# KeyChaininoTHT.net
KiCad netlist of a schematic drawn in EAGLE
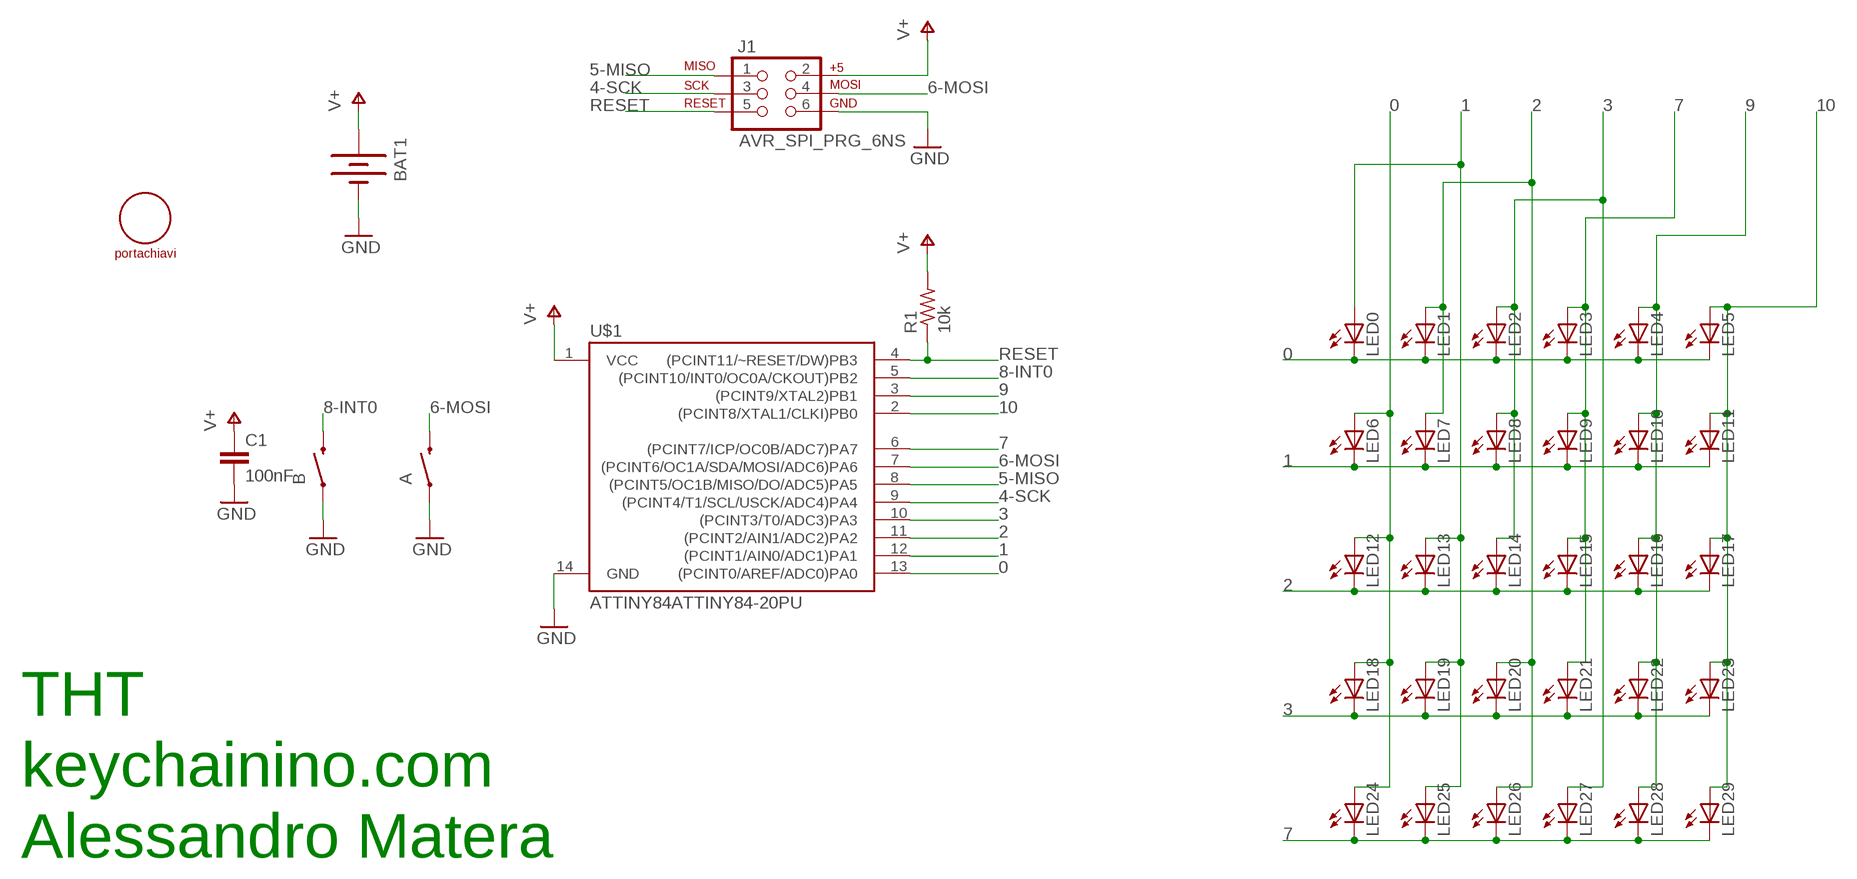
[diagram p0: schematic, sheet 1]

(export (version "E")
  (design (tool "Eeschema 10.0.6"))
  (components
    (comp (ref "A")
      (value "SWITCH-MOMENTARY-2PTH")
      (footprint "eagle-import:TACTILE-PTH")
      (libsource (lib "eagle-import") (part "SWITCH-MOMENTARY-2PTH"))
    )
    (comp (ref "B")
      (value "SWITCH-MOMENTARY-2PTH")
      (footprint "eagle-import:TACTILE-PTH")
      (libsource (lib "eagle-import") (part "SWITCH-MOMENTARY-2PTH"))
    )
    (comp (ref "BAT1")
      (value "BATTERY20PTH")
      (footprint "eagle-import:BATTCOM_20MM_PTH")
      (libsource (lib "eagle-import") (part "BATTERY20PTH"))
    )
    (comp (ref "C1")
      (value "100nF")
      (footprint "eagle-import:CAP-PTH-5MM")
      (libsource (lib "eagle-import") (part "CAPPTH1"))
    )
    (comp (ref "J1")
      (value "AVR_SPI_PRG_6NS")
      (footprint "eagle-import:2X3-NS")
      (libsource (lib "eagle-import") (part "AVR_SPI_PRG_6NS"))
    )
    (comp (ref "LED0")
      (value "LED5MM-KIT")
      (footprint "eagle-import:LED5MM-KIT")
      (libsource (lib "eagle-import") (part "LED5MM-KIT"))
    )
    (comp (ref "LED1")
      (value "LED5MM-KIT")
      (footprint "eagle-import:LED5MM-KIT")
      (libsource (lib "eagle-import") (part "LED5MM-KIT"))
    )
    (comp (ref "LED2")
      (value "LED5MM-KIT")
      (footprint "eagle-import:LED5MM-KIT")
      (libsource (lib "eagle-import") (part "LED5MM-KIT"))
    )
    (comp (ref "LED3")
      (value "LED5MM-KIT")
      (footprint "eagle-import:LED5MM-KIT")
      (libsource (lib "eagle-import") (part "LED5MM-KIT"))
    )
    (comp (ref "LED4")
      (value "LED5MM-KIT")
      (footprint "eagle-import:LED5MM-KIT")
      (libsource (lib "eagle-import") (part "LED5MM-KIT"))
    )
    (comp (ref "LED5")
      (value "LED5MM-KIT")
      (footprint "eagle-import:LED5MM-KIT")
      (libsource (lib "eagle-import") (part "LED5MM-KIT"))
    )
    (comp (ref "LED6")
      (value "LED5MM-KIT")
      (footprint "eagle-import:LED5MM-KIT")
      (libsource (lib "eagle-import") (part "LED5MM-KIT"))
    )
    (comp (ref "LED7")
      (value "LED5MM-KIT")
      (footprint "eagle-import:LED5MM-KIT")
      (libsource (lib "eagle-import") (part "LED5MM-KIT"))
    )
    (comp (ref "LED8")
      (value "LED5MM-KIT")
      (footprint "eagle-import:LED5MM-KIT")
      (libsource (lib "eagle-import") (part "LED5MM-KIT"))
    )
    (comp (ref "LED9")
      (value "LED5MM-KIT")
      (footprint "eagle-import:LED5MM-KIT")
      (libsource (lib "eagle-import") (part "LED5MM-KIT"))
    )
    (comp (ref "LED10")
      (value "LED5MM-KIT")
      (footprint "eagle-import:LED5MM-KIT")
      (libsource (lib "eagle-import") (part "LED5MM-KIT"))
    )
    (comp (ref "LED11")
      (value "LED5MM-KIT")
      (footprint "eagle-import:LED5MM-KIT")
      (libsource (lib "eagle-import") (part "LED5MM-KIT"))
    )
    (comp (ref "LED12")
      (value "LED5MM-KIT")
      (footprint "eagle-import:LED5MM-KIT")
      (libsource (lib "eagle-import") (part "LED5MM-KIT"))
    )
    (comp (ref "LED13")
      (value "LED5MM-KIT")
      (footprint "eagle-import:LED5MM-KIT")
      (libsource (lib "eagle-import") (part "LED5MM-KIT"))
    )
    (comp (ref "LED14")
      (value "LED5MM-KIT")
      (footprint "eagle-import:LED5MM-KIT")
      (libsource (lib "eagle-import") (part "LED5MM-KIT"))
    )
    (comp (ref "LED15")
      (value "LED5MM-KIT")
      (footprint "eagle-import:LED5MM-KIT")
      (libsource (lib "eagle-import") (part "LED5MM-KIT"))
    )
    (comp (ref "LED16")
      (value "LED5MM-KIT")
      (footprint "eagle-import:LED5MM-KIT")
      (libsource (lib "eagle-import") (part "LED5MM-KIT"))
    )
    (comp (ref "LED17")
      (value "LED5MM-KIT")
      (footprint "eagle-import:LED5MM-KIT")
      (libsource (lib "eagle-import") (part "LED5MM-KIT"))
    )
    (comp (ref "LED18")
      (value "LED5MM-KIT")
      (footprint "eagle-import:LED5MM-KIT")
      (libsource (lib "eagle-import") (part "LED5MM-KIT"))
    )
    (comp (ref "LED19")
      (value "LED5MM-KIT")
      (footprint "eagle-import:LED5MM-KIT")
      (libsource (lib "eagle-import") (part "LED5MM-KIT"))
    )
    (comp (ref "LED20")
      (value "LED5MM-KIT")
      (footprint "eagle-import:LED5MM-KIT")
      (libsource (lib "eagle-import") (part "LED5MM-KIT"))
    )
    (comp (ref "LED21")
      (value "LED5MM-KIT")
      (footprint "eagle-import:LED5MM-KIT")
      (libsource (lib "eagle-import") (part "LED5MM-KIT"))
    )
    (comp (ref "LED22")
      (value "LED5MM-KIT")
      (footprint "eagle-import:LED5MM-KIT")
      (libsource (lib "eagle-import") (part "LED5MM-KIT"))
    )
    (comp (ref "LED23")
      (value "LED5MM-KIT")
      (footprint "eagle-import:LED5MM-KIT")
      (libsource (lib "eagle-import") (part "LED5MM-KIT"))
    )
    (comp (ref "LED24")
      (value "LED5MM-KIT")
      (footprint "eagle-import:LED5MM-KIT")
      (libsource (lib "eagle-import") (part "LED5MM-KIT"))
    )
    (comp (ref "LED25")
      (value "LED5MM-KIT")
      (footprint "eagle-import:LED5MM-KIT")
      (libsource (lib "eagle-import") (part "LED5MM-KIT"))
    )
    (comp (ref "LED26")
      (value "LED5MM-KIT")
      (footprint "eagle-import:LED5MM-KIT")
      (libsource (lib "eagle-import") (part "LED5MM-KIT"))
    )
    (comp (ref "LED27")
      (value "LED5MM-KIT")
      (footprint "eagle-import:LED5MM-KIT")
      (libsource (lib "eagle-import") (part "LED5MM-KIT"))
    )
    (comp (ref "LED28")
      (value "LED5MM-KIT")
      (footprint "eagle-import:LED5MM-KIT")
      (libsource (lib "eagle-import") (part "LED5MM-KIT"))
    )
    (comp (ref "LED29")
      (value "LED5MM-KIT")
      (footprint "eagle-import:LED5MM-KIT")
      (libsource (lib "eagle-import") (part "LED5MM-KIT"))
    )
    (comp (ref "R1")
      (value "10k")
      (footprint "eagle-import:R1206")
      (libsource (lib "eagle-import") (part "R-US_R1206"))
    )
    (comp (ref "U$1")
      (value "ATTINY84ATTINY84-20PU")
      (footprint "eagle-import:DIL14")
      (libsource (lib "eagle-import") (part "ATTINY84ATTINY84-20PU"))
    )
    (comp (ref "U$2")
      (value "ANELLO-PORTACHIAVI")
      (footprint "eagle-import:HOLE-PORTACHIAVI")
      (libsource (lib "eagle-import") (part "ANELLO-PORTACHIAVI"))
    )
  )
  (nets
    (net (code "1") (name "/0") (class "Default")
      (node (ref "LED0") (pin "K") (pinfunction "C_K") (pintype "passive"))
      (node (ref "LED1") (pin "K") (pinfunction "C_K") (pintype "passive"))
      (node (ref "LED12") (pin "A") (pinfunction "A_A") (pintype "passive"))
      (node (ref "LED18") (pin "A") (pinfunction "A_A") (pintype "passive"))
      (node (ref "LED2") (pin "K") (pinfunction "C_K") (pintype "passive"))
      (node (ref "LED24") (pin "A") (pinfunction "A_A") (pintype "passive"))
      (node (ref "LED3") (pin "K") (pinfunction "C_K") (pintype "passive"))
      (node (ref "LED4") (pin "K") (pinfunction "C_K") (pintype "passive"))
      (node (ref "LED5") (pin "K") (pinfunction "C_K") (pintype "passive"))
      (node (ref "LED6") (pin "A") (pinfunction "A_A") (pintype "passive"))
      (node (ref "U$1") (pin "13") (pinfunction "(PCINT0/AREF/ADC0)PA0_13") (pintype "bidirectional"))
    )
    (net (code "2") (name "/1") (class "Default")
      (node (ref "LED0") (pin "A") (pinfunction "A_A") (pintype "passive"))
      (node (ref "LED10") (pin "K") (pinfunction "C_K") (pintype "passive"))
      (node (ref "LED11") (pin "K") (pinfunction "C_K") (pintype "passive"))
      (node (ref "LED13") (pin "A") (pinfunction "A_A") (pintype "passive"))
      (node (ref "LED19") (pin "A") (pinfunction "A_A") (pintype "passive"))
      (node (ref "LED25") (pin "A") (pinfunction "A_A") (pintype "passive"))
      (node (ref "LED6") (pin "K") (pinfunction "C_K") (pintype "passive"))
      (node (ref "LED7") (pin "K") (pinfunction "C_K") (pintype "passive"))
      (node (ref "LED8") (pin "K") (pinfunction "C_K") (pintype "passive"))
      (node (ref "LED9") (pin "K") (pinfunction "C_K") (pintype "passive"))
      (node (ref "U$1") (pin "12") (pinfunction "(PCINT1/AIN0/ADC1)PA1_12") (pintype "bidirectional"))
    )
    (net (code "3") (name "/2") (class "Default")
      (node (ref "LED1") (pin "A") (pinfunction "A_A") (pintype "passive"))
      (node (ref "LED12") (pin "K") (pinfunction "C_K") (pintype "passive"))
      (node (ref "LED13") (pin "K") (pinfunction "C_K") (pintype "passive"))
      (node (ref "LED14") (pin "K") (pinfunction "C_K") (pintype "passive"))
      (node (ref "LED15") (pin "K") (pinfunction "C_K") (pintype "passive"))
      (node (ref "LED16") (pin "K") (pinfunction "C_K") (pintype "passive"))
      (node (ref "LED17") (pin "K") (pinfunction "C_K") (pintype "passive"))
      (node (ref "LED20") (pin "A") (pinfunction "A_A") (pintype "passive"))
      (node (ref "LED26") (pin "A") (pinfunction "A_A") (pintype "passive"))
      (node (ref "LED7") (pin "A") (pinfunction "A_A") (pintype "passive"))
      (node (ref "U$1") (pin "11") (pinfunction "(PCINT2/AIN1/ADC2)PA2_11") (pintype "bidirectional"))
    )
    (net (code "4") (name "/3") (class "Default")
      (node (ref "LED14") (pin "A") (pinfunction "A_A") (pintype "passive"))
      (node (ref "LED18") (pin "K") (pinfunction "C_K") (pintype "passive"))
      (node (ref "LED19") (pin "K") (pinfunction "C_K") (pintype "passive"))
      (node (ref "LED2") (pin "A") (pinfunction "A_A") (pintype "passive"))
      (node (ref "LED20") (pin "K") (pinfunction "C_K") (pintype "passive"))
      (node (ref "LED21") (pin "K") (pinfunction "C_K") (pintype "passive"))
      (node (ref "LED22") (pin "K") (pinfunction "C_K") (pintype "passive"))
      (node (ref "LED23") (pin "K") (pinfunction "C_K") (pintype "passive"))
      (node (ref "LED27") (pin "A") (pinfunction "A_A") (pintype "passive"))
      (node (ref "LED8") (pin "A") (pinfunction "A_A") (pintype "passive"))
      (node (ref "U$1") (pin "10") (pinfunction "(PCINT3/T0/ADC3)PA3_10") (pintype "bidirectional"))
    )
    (net (code "5") (name "/4-SCK") (class "Default")
      (node (ref "J1") (pin "3") (pinfunction "3_3") (pintype "passive"))
      (node (ref "U$1") (pin "9") (pinfunction "(PCINT4/T1/SCL/USCK/ADC4)PA4_9") (pintype "bidirectional"))
    )
    (net (code "6") (name "/5-MISO") (class "Default")
      (node (ref "J1") (pin "1") (pinfunction "1_1") (pintype "passive"))
      (node (ref "U$1") (pin "8") (pinfunction "(PCINT5/OC1B/MISO/DO/ADC5)PA5_8") (pintype "bidirectional"))
    )
    (net (code "7") (name "/6-MOSI") (class "Default")
      (node (ref "A") (pin "3") (pinfunction "2_3") (pintype "passive"))
      (node (ref "J1") (pin "4") (pinfunction "4_4") (pintype "passive"))
      (node (ref "U$1") (pin "7") (pinfunction "(PCINT6/OC1A/SDA/MOSI/ADC6)PA6_7") (pintype "bidirectional"))
    )
    (net (code "8") (name "/7") (class "Default")
      (node (ref "LED15") (pin "A") (pinfunction "A_A") (pintype "passive"))
      (node (ref "LED21") (pin "A") (pinfunction "A_A") (pintype "passive"))
      (node (ref "LED24") (pin "K") (pinfunction "C_K") (pintype "passive"))
      (node (ref "LED25") (pin "K") (pinfunction "C_K") (pintype "passive"))
      (node (ref "LED26") (pin "K") (pinfunction "C_K") (pintype "passive"))
      (node (ref "LED27") (pin "K") (pinfunction "C_K") (pintype "passive"))
      (node (ref "LED28") (pin "K") (pinfunction "C_K") (pintype "passive"))
      (node (ref "LED29") (pin "K") (pinfunction "C_K") (pintype "passive"))
      (node (ref "LED3") (pin "A") (pinfunction "A_A") (pintype "passive"))
      (node (ref "LED9") (pin "A") (pinfunction "A_A") (pintype "passive"))
      (node (ref "U$1") (pin "6") (pinfunction "(PCINT7/ICP/OC0B/ADC7)PA7_6") (pintype "bidirectional"))
    )
    (net (code "9") (name "/8-INT0") (class "Default")
      (node (ref "B") (pin "3") (pinfunction "2_3") (pintype "passive"))
      (node (ref "U$1") (pin "5") (pinfunction "(PCINT10/INT0/OC0A/CKOUT)PB2_5") (pintype "bidirectional"))
    )
    (net (code "10") (name "/9") (class "Default")
      (node (ref "LED10") (pin "A") (pinfunction "A_A") (pintype "passive"))
      (node (ref "LED16") (pin "A") (pinfunction "A_A") (pintype "passive"))
      (node (ref "LED22") (pin "A") (pinfunction "A_A") (pintype "passive"))
      (node (ref "LED28") (pin "A") (pinfunction "A_A") (pintype "passive"))
      (node (ref "LED4") (pin "A") (pinfunction "A_A") (pintype "passive"))
      (node (ref "U$1") (pin "3") (pinfunction "(PCINT9/XTAL2)PB1_3") (pintype "bidirectional"))
    )
    (net (code "11") (name "/10") (class "Default")
      (node (ref "LED11") (pin "A") (pinfunction "A_A") (pintype "passive"))
      (node (ref "LED17") (pin "A") (pinfunction "A_A") (pintype "passive"))
      (node (ref "LED23") (pin "A") (pinfunction "A_A") (pintype "passive"))
      (node (ref "LED29") (pin "A") (pinfunction "A_A") (pintype "passive"))
      (node (ref "LED5") (pin "A") (pinfunction "A_A") (pintype "passive"))
      (node (ref "U$1") (pin "2") (pinfunction "(PCINT8/XTAL1/CLKI)PB0_2") (pintype "bidirectional"))
    )
    (net (code "12") (name "/RESET") (class "Default")
      (node (ref "J1") (pin "5") (pinfunction "5_5") (pintype "passive"))
      (node (ref "R1") (pin "1") (pinfunction "1_1") (pintype "passive"))
      (node (ref "U$1") (pin "4") (pinfunction "(PCINT11/~{RESET/DW})PB3_4") (pintype "bidirectional"))
    )
    (net (code "13") (name "GND") (class "Default")
      (node (ref "A") (pin "1") (pinfunction "1_1") (pintype "passive"))
      (node (ref "B") (pin "1") (pinfunction "1_1") (pintype "passive"))
      (node (ref "BAT1") (pin "2") (pinfunction "-_2") (pintype "power_in"))
      (node (ref "C1") (pin "2") (pinfunction "2_2") (pintype "passive"))
      (node (ref "J1") (pin "6") (pinfunction "6_6") (pintype "passive"))
      (node (ref "U$1") (pin "14") (pinfunction "GND_14") (pintype "bidirectional"))
    )
    (net (code "14") (name "V+") (class "Default")
      (node (ref "BAT1") (pin "1") (pinfunction "+_1") (pintype "power_in"))
      (node (ref "C1") (pin "1") (pinfunction "1_1") (pintype "passive"))
      (node (ref "J1") (pin "2") (pinfunction "2_2") (pintype "passive"))
      (node (ref "R1") (pin "2") (pinfunction "2_2") (pintype "passive"))
      (node (ref "U$1") (pin "1") (pinfunction "VCC_1") (pintype "bidirectional"))
    )
  )
)
